# gyroscope.net
KiCad netlist of a schematic drawn in Altium Designer
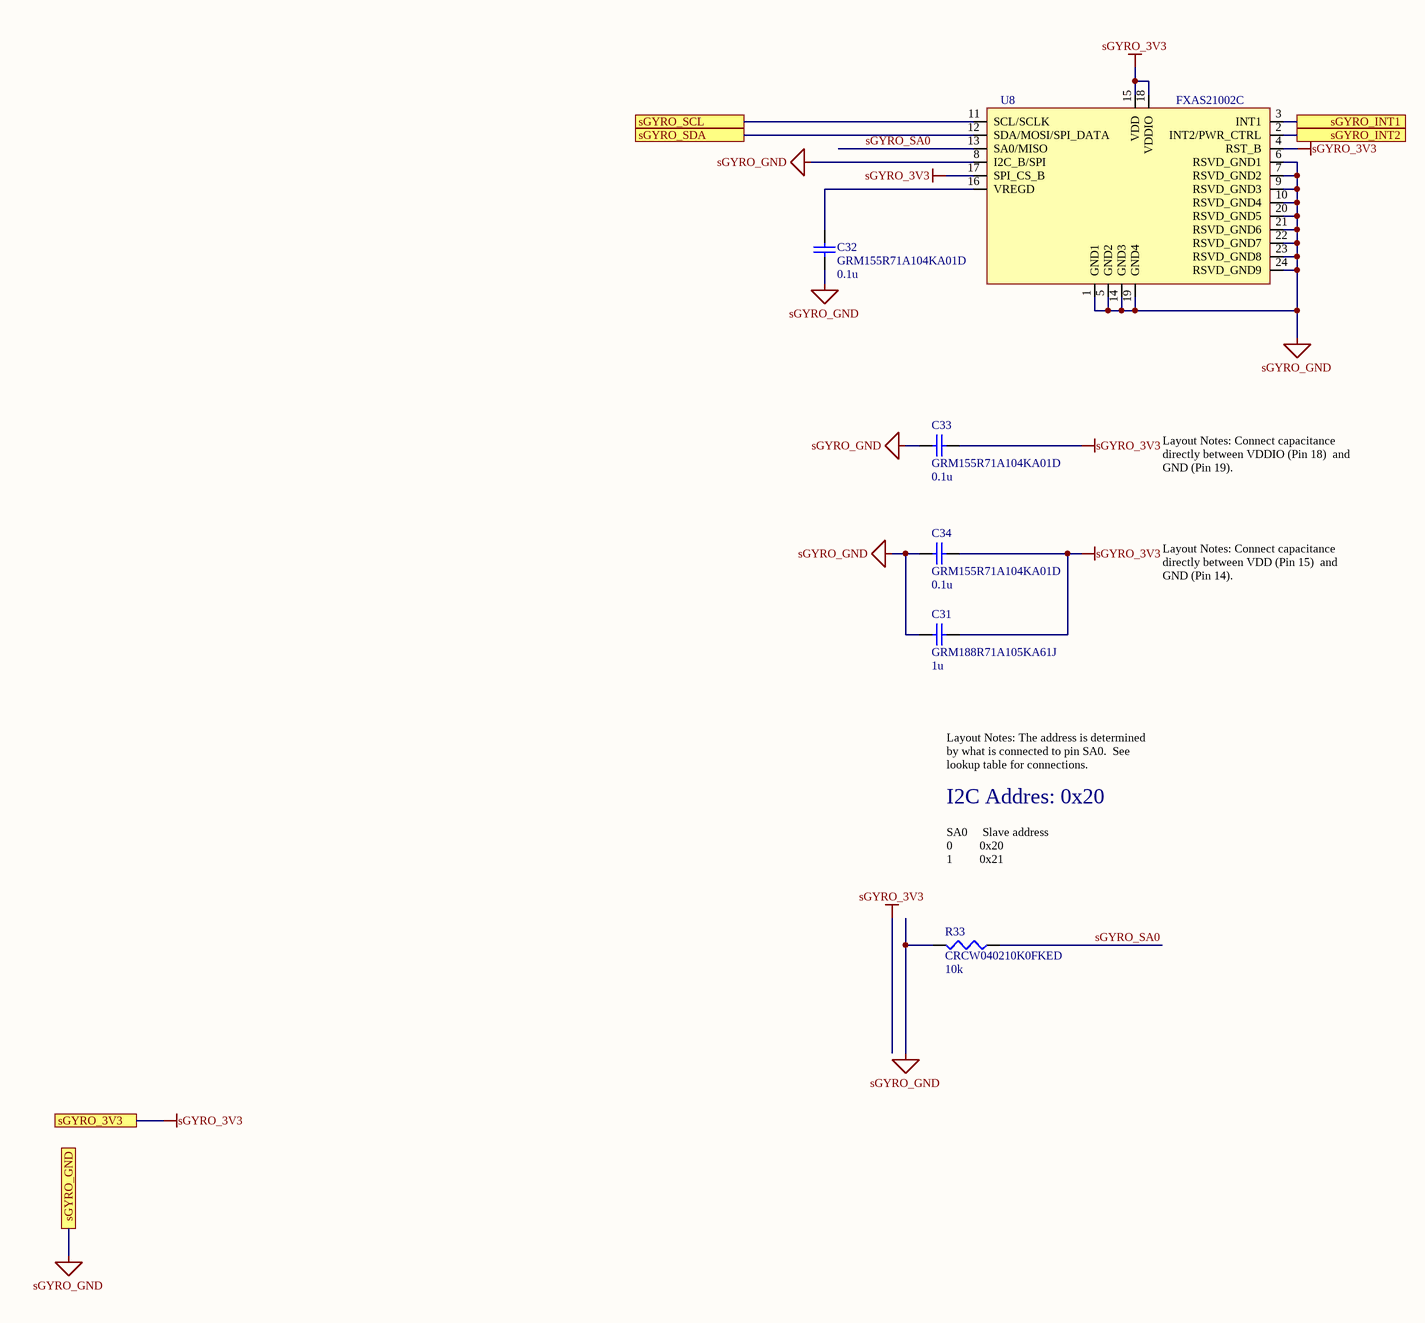
[diagram p0: _gyroscope.SchDoc]

(export (version "E")
  (design (tool "Eeschema 10.0.6"))
  (components
    (comp (ref "C31")
      (value "GRM188R71A105KA61J")
      (footprint "0603")
      (description "-55-125C, 1608, 10V, X7R, ±10%")
      (fields (field (name "ALTIUM_VALUE") "1u"))
      (libsource (lib "standard_capacitors") (part "GRM188R71AxxxKdddd"))
    )
    (comp (ref "C32")
      (value "GRM155R71A104KA01D")
      (footprint "0402")
      (description "-55-125C, 1005, 10V, X7R, ±10%")
      (fields (field (name "ALTIUM_VALUE") "0.1u"))
      (libsource (lib "standard_capacitors") (part "GRM155R71AxxxKdddd"))
    )
    (comp (ref "C33")
      (value "GRM155R71A104KA01D")
      (footprint "0402")
      (description "-55-125C, 1005, 10V, X7R, ±10%")
      (fields (field (name "ALTIUM_VALUE") "0.1u"))
      (libsource (lib "standard_capacitors") (part "GRM155R71AxxxKdddd"))
    )
    (comp (ref "C34")
      (value "GRM155R71A104KA01D")
      (footprint "0402")
      (description "-55-125C, 1005, 10V, X7R, ±10%")
      (fields (field (name "ALTIUM_VALUE") "0.1u"))
      (libsource (lib "standard_capacitors") (part "GRM155R71AxxxKdddd"))
    )
    (comp (ref "R33")
      (value "CRCW040210K0FKED")
      (footprint "0402")
      (description "0.125W, -55-155C, 1005, 50V, ±1%")
      (fields (field (name "ALTIUM_VALUE") "10k"))
      (libsource (lib "standard_resistors") (part "CRCW0402xxxxFKED"))
    )
    (comp (ref "U8")
      (value "FXAS21002C")
      (footprint "SMD QFN 24_4X4MM 7/5")
      (description "3-Axis Digital Angular Rate  Gyroscope")
      (libsource (lib "nxp") (part "FXAS21002C"))
    )
  )
  (nets
    (net (code "1") (name "/sGYRO_INT1") (class "Default")
      (node (ref "U8") (pin "3") (pinfunction "INT1_3") (pintype "passive"))
    )
    (net (code "2") (name "/sGYRO_INT2") (class "Default")
      (node (ref "U8") (pin "2") (pinfunction "INT2/PWR_CTRL_2") (pintype "passive"))
    )
    (net (code "3") (name "/sGYRO_SA0") (class "Default")
      (node (ref "R33") (pin "1") (pinfunction "1_1") (pintype "passive"))
      (node (ref "U8") (pin "13") (pinfunction "SA0/MISO_13") (pintype "passive"))
    )
    (net (code "4") (name "/sGYRO_SCL") (class "Default")
      (node (ref "U8") (pin "11") (pinfunction "SCL/SCLK_11") (pintype "passive"))
    )
    (net (code "5") (name "/sGYRO_SDA") (class "Default")
      (node (ref "U8") (pin "12") (pinfunction "SDA/MOSI/SPI_DATA_12") (pintype "passive"))
    )
    (net (code "6") (name "Net-(U8-VREGD)") (class "Default")
      (node (ref "C32") (pin "1") (pinfunction "1_1") (pintype "passive"))
      (node (ref "U8") (pin "16") (pinfunction "VREGD_16") (pintype "passive"))
    )
    (net (code "7") (name "sGYRO_3V3") (class "Default")
      (node (ref "C31") (pin "1") (pinfunction "1_1") (pintype "passive"))
      (node (ref "C33") (pin "2") (pinfunction "2_2") (pintype "passive"))
      (node (ref "C34") (pin "2") (pinfunction "2_2") (pintype "passive"))
      (node (ref "U8") (pin "15") (pinfunction "VDD_15") (pintype "passive"))
      (node (ref "U8") (pin "17") (pinfunction "SPI_CS_B_17") (pintype "passive"))
      (node (ref "U8") (pin "18") (pinfunction "VDDIO_18") (pintype "passive"))
      (node (ref "U8") (pin "4") (pinfunction "RST_B_4") (pintype "passive"))
    )
    (net (code "8") (name "sGYRO_GND") (class "Default")
      (node (ref "C31") (pin "2") (pinfunction "2_2") (pintype "passive"))
      (node (ref "C32") (pin "2") (pinfunction "2_2") (pintype "passive"))
      (node (ref "C33") (pin "1") (pinfunction "1_1") (pintype "passive"))
      (node (ref "C34") (pin "1") (pinfunction "1_1") (pintype "passive"))
      (node (ref "R33") (pin "2") (pinfunction "2_2") (pintype "passive"))
      (node (ref "U8") (pin "1") (pinfunction "GND1_1") (pintype "passive"))
      (node (ref "U8") (pin "10") (pinfunction "RSVD_GND4_10") (pintype "passive"))
      (node (ref "U8") (pin "14") (pinfunction "GND3_14") (pintype "passive"))
      (node (ref "U8") (pin "19") (pinfunction "GND4_19") (pintype "passive"))
      (node (ref "U8") (pin "20") (pinfunction "RSVD_GND5_20") (pintype "passive"))
      (node (ref "U8") (pin "21") (pinfunction "RSVD_GND6_21") (pintype "passive"))
      (node (ref "U8") (pin "22") (pinfunction "RSVD_GND7_22") (pintype "passive"))
      (node (ref "U8") (pin "23") (pinfunction "RSVD_GND8_23") (pintype "passive"))
      (node (ref "U8") (pin "24") (pinfunction "RSVD_GND9_24") (pintype "passive"))
      (node (ref "U8") (pin "5") (pinfunction "GND2_5") (pintype "passive"))
      (node (ref "U8") (pin "6") (pinfunction "RSVD_GND1_6") (pintype "passive"))
      (node (ref "U8") (pin "7") (pinfunction "RSVD_GND2_7") (pintype "passive"))
      (node (ref "U8") (pin "8") (pinfunction "I2C_B/SPI_8") (pintype "passive"))
      (node (ref "U8") (pin "9") (pinfunction "RSVD_GND3_9") (pintype "passive"))
    )
  )
)
